# SCH_usb-hub_2024-06-29.net
KiCad netlist of a schematic drawn in EasyEDA
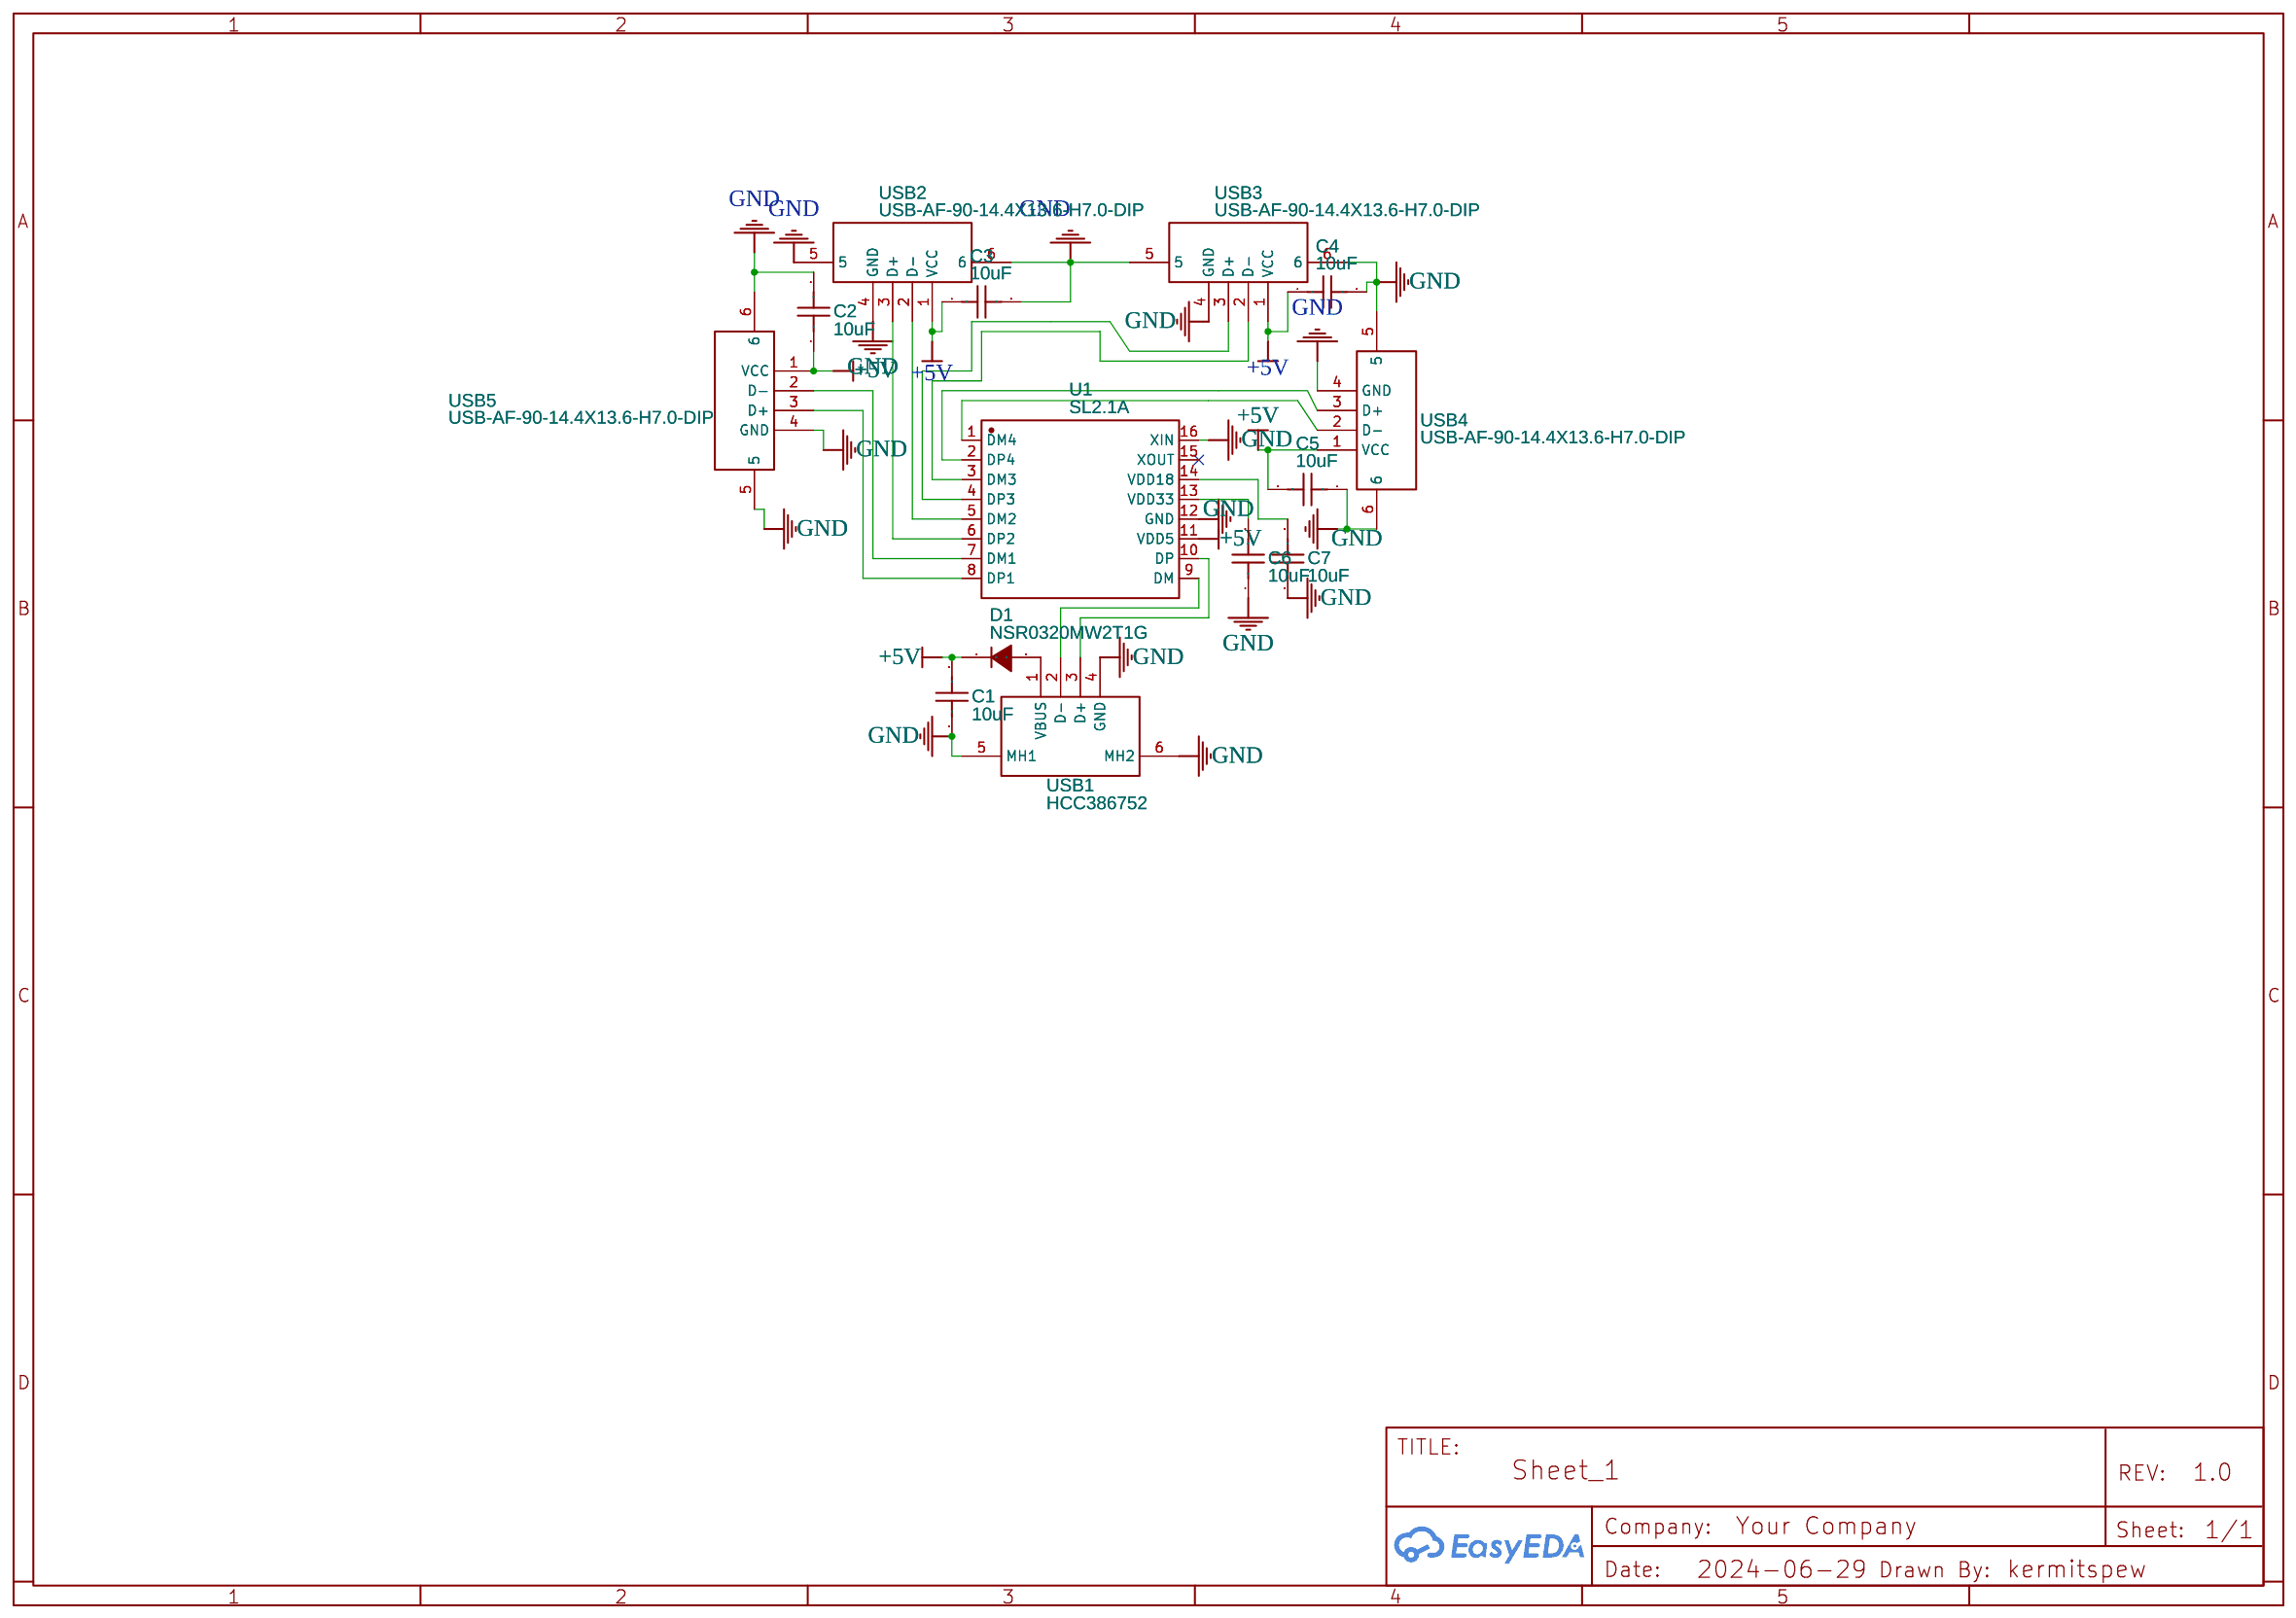
[diagram p0: schematic sheet]

(export (version "E")
  (design (tool "Eeschema 10.0.6"))
  (components
    (comp (ref "C1")
      (value "10uF")
      (fields
        (field (name "Manufacturer Part") "CL10A106KP8NNNC")
        (field (name "Manufacturer") "SAMSUNG(三星)")
      )
      (libsource (lib "") (part "CL10A106KP8NNNC_1"))
    )
    (comp (ref "C2")
      (value "10uF")
      (fields
        (field (name "Manufacturer Part") "CL10A106KP8NNNC")
        (field (name "Manufacturer") "SAMSUNG(三星)")
      )
      (libsource (lib "") (part "CL10A106KP8NNNC_1"))
    )
    (comp (ref "C3")
      (value "10uF")
      (fields
        (field (name "Manufacturer Part") "CL10A106KP8NNNC")
        (field (name "Manufacturer") "SAMSUNG(三星)")
      )
      (libsource (lib "") (part "CL10A106KP8NNNC_2"))
    )
    (comp (ref "C4")
      (value "10uF")
      (fields
        (field (name "Manufacturer Part") "CL10A106KP8NNNC")
        (field (name "Manufacturer") "SAMSUNG(三星)")
      )
      (libsource (lib "") (part "CL10A106KP8NNNC_2"))
    )
    (comp (ref "C5")
      (value "10uF")
      (fields
        (field (name "Manufacturer Part") "CL10A106KP8NNNC")
        (field (name "Manufacturer") "SAMSUNG(三星)")
      )
      (libsource (lib "") (part "CL10A106KP8NNNC"))
    )
    (comp (ref "C6")
      (value "10uF")
      (fields
        (field (name "Manufacturer Part") "CL10A106KP8NNNC")
        (field (name "Manufacturer") "SAMSUNG(三星)")
      )
      (libsource (lib "") (part "CL10A106KP8NNNC_1"))
    )
    (comp (ref "C7")
      (value "10uF")
      (fields
        (field (name "Manufacturer Part") "CL10A106KP8NNNC")
        (field (name "Manufacturer") "SAMSUNG(三星)")
      )
      (libsource (lib "") (part "CL10A106KP8NNNC_1"))
    )
    (comp (ref "D1")
      (value "NSR0320MW2T1G")
      (fields (field (name "Manufacturer") "onsemi(安森美)"))
      (libsource (lib "") (part "NSR0320MW2T1G"))
    )
    (comp (ref "U1")
      (value "SL2.1A")
      (fields (field (name "Manufacturer") "CoreChips(和芯润德)"))
      (libsource (lib "") (part "SL2.1A"))
    )
    (comp (ref "USB1")
      (value "HCC386752")
      (fields (field (name "Manufacturer Part") "U-USBAR04P-M003") (field (name "Manufacturer") "Ckmtw(灿科盟)"))
      (libsource (lib "") (part "HCC386752"))
    )
    (comp (ref "USB2")
      (value "USB-AF-90-14.4X13.6-H7.0-DIP")
      (fields (field (name "Manufacturer Part") "903-131A1011D10100") (field (name "Manufacturer") "精拓金"))
      (libsource (lib "") (part "USB-AF-90-14.4X13.6-H7.0-DIP_2"))
    )
    (comp (ref "USB3")
      (value "USB-AF-90-14.4X13.6-H7.0-DIP")
      (fields (field (name "Manufacturer Part") "903-131A1011D10100") (field (name "Manufacturer") "精拓金"))
      (libsource (lib "") (part "USB-AF-90-14.4X13.6-H7.0-DIP_2"))
    )
    (comp (ref "USB4")
      (value "USB-AF-90-14.4X13.6-H7.0-DIP")
      (fields (field (name "Manufacturer Part") "903-131A1011D10100") (field (name "Manufacturer") "精拓金"))
      (libsource (lib "") (part "USB-AF-90-14.4X13.6-H7.0-DIP_1"))
    )
    (comp (ref "USB5")
      (value "USB-AF-90-14.4X13.6-H7.0-DIP")
      (fields (field (name "Manufacturer Part") "903-131A1011D10100") (field (name "Manufacturer") "精拓金"))
      (libsource (lib "") (part "USB-AF-90-14.4X13.6-H7.0-DIP"))
    )
  )
  (nets
    (net (code "1") (name "+5V") (class "Default")
      (node (ref "C1") (pin "2") (pinfunction "2_2") (pintype "unspecified"))
      (node (ref "C2") (pin "1") (pinfunction "1_1") (pintype "unspecified"))
      (node (ref "C3") (pin "1") (pinfunction "1_1") (pintype "unspecified"))
      (node (ref "C4") (pin "1") (pinfunction "1_1") (pintype "unspecified"))
      (node (ref "C5") (pin "2") (pinfunction "2_2") (pintype "unspecified"))
      (node (ref "D1") (pin "1") (pinfunction "C_1") (pintype "unspecified"))
      (node (ref "U1") (pin "11") (pinfunction "VDD5_11") (pintype "unspecified"))
      (node (ref "USB2") (pin "1") (pinfunction "VCC_1") (pintype "unspecified"))
      (node (ref "USB3") (pin "1") (pinfunction "VCC_1") (pintype "unspecified"))
      (node (ref "USB4") (pin "1") (pinfunction "VCC_1") (pintype "unspecified"))
      (node (ref "USB5") (pin "1") (pinfunction "VCC_1") (pintype "unspecified"))
    )
    (net (code "2") (name "GND") (class "Default")
      (node (ref "C1") (pin "1") (pinfunction "1_1") (pintype "unspecified"))
      (node (ref "C2") (pin "2") (pinfunction "2_2") (pintype "unspecified"))
      (node (ref "C3") (pin "2") (pinfunction "2_2") (pintype "unspecified"))
      (node (ref "C4") (pin "2") (pinfunction "2_2") (pintype "unspecified"))
      (node (ref "C5") (pin "1") (pinfunction "1_1") (pintype "unspecified"))
      (node (ref "C6") (pin "1") (pinfunction "1_1") (pintype "unspecified"))
      (node (ref "C7") (pin "1") (pinfunction "1_1") (pintype "unspecified"))
      (node (ref "U1") (pin "12") (pinfunction "GND_12") (pintype "unspecified"))
      (node (ref "U1") (pin "16") (pinfunction "XIN_16") (pintype "unspecified"))
      (node (ref "USB1") (pin "4") (pinfunction "GND_4") (pintype "unspecified"))
      (node (ref "USB1") (pin "5") (pinfunction "MH1_5") (pintype "unspecified"))
      (node (ref "USB1") (pin "6") (pinfunction "MH2_6") (pintype "unspecified"))
      (node (ref "USB2") (pin "4") (pinfunction "GND_4") (pintype "unspecified"))
      (node (ref "USB2") (pin "5") (pinfunction "5_5") (pintype "unspecified"))
      (node (ref "USB2") (pin "6") (pinfunction "6_6") (pintype "unspecified"))
      (node (ref "USB3") (pin "4") (pinfunction "GND_4") (pintype "unspecified"))
      (node (ref "USB3") (pin "5") (pinfunction "5_5") (pintype "unspecified"))
      (node (ref "USB3") (pin "6") (pinfunction "6_6") (pintype "unspecified"))
      (node (ref "USB4") (pin "4") (pinfunction "GND_4") (pintype "unspecified"))
      (node (ref "USB4") (pin "5") (pinfunction "5_5") (pintype "unspecified"))
      (node (ref "USB4") (pin "6") (pinfunction "6_6") (pintype "unspecified"))
      (node (ref "USB5") (pin "4") (pinfunction "GND_4") (pintype "unspecified"))
      (node (ref "USB5") (pin "5") (pinfunction "5_5") (pintype "unspecified"))
      (node (ref "USB5") (pin "6") (pinfunction "6_6") (pintype "unspecified"))
    )
    (net (code "3") (name "Net-(D1-A)") (class "Default")
      (node (ref "D1") (pin "2") (pinfunction "A_2") (pintype "unspecified"))
      (node (ref "USB1") (pin "1") (pinfunction "VBUS_1") (pintype "unspecified"))
    )
    (net (code "4") (name "Net-(U1-DM)") (class "Default")
      (node (ref "U1") (pin "9") (pinfunction "DM_9") (pintype "unspecified"))
      (node (ref "USB1") (pin "2") (pinfunction "D-_2") (pintype "unspecified"))
    )
    (net (code "5") (name "Net-(U1-DM1)") (class "Default")
      (node (ref "U1") (pin "7") (pinfunction "DM1_7") (pintype "unspecified"))
      (node (ref "USB5") (pin "2") (pinfunction "D-_2") (pintype "unspecified"))
    )
    (net (code "6") (name "Net-(U1-DM2)") (class "Default")
      (node (ref "U1") (pin "5") (pinfunction "DM2_5") (pintype "unspecified"))
      (node (ref "USB2") (pin "2") (pinfunction "D-_2") (pintype "unspecified"))
    )
    (net (code "7") (name "Net-(U1-DM3)") (class "Default")
      (node (ref "U1") (pin "3") (pinfunction "DM3_3") (pintype "unspecified"))
      (node (ref "USB3") (pin "2") (pinfunction "D-_2") (pintype "unspecified"))
    )
    (net (code "8") (name "Net-(U1-DM4)") (class "Default")
      (node (ref "U1") (pin "1") (pinfunction "DM4_1") (pintype "unspecified"))
      (node (ref "USB4") (pin "2") (pinfunction "D-_2") (pintype "unspecified"))
    )
    (net (code "9") (name "Net-(U1-DP)") (class "Default")
      (node (ref "U1") (pin "10") (pinfunction "DP_10") (pintype "unspecified"))
      (node (ref "USB1") (pin "3") (pinfunction "D+_3") (pintype "unspecified"))
    )
    (net (code "10") (name "Net-(U1-DP1)") (class "Default")
      (node (ref "U1") (pin "8") (pinfunction "DP1_8") (pintype "unspecified"))
      (node (ref "USB5") (pin "3") (pinfunction "D+_3") (pintype "unspecified"))
    )
    (net (code "11") (name "Net-(U1-DP2)") (class "Default")
      (node (ref "U1") (pin "6") (pinfunction "DP2_6") (pintype "unspecified"))
      (node (ref "USB2") (pin "3") (pinfunction "D+_3") (pintype "unspecified"))
    )
    (net (code "12") (name "Net-(U1-DP3)") (class "Default")
      (node (ref "U1") (pin "4") (pinfunction "DP3_4") (pintype "unspecified"))
      (node (ref "USB3") (pin "3") (pinfunction "D+_3") (pintype "unspecified"))
    )
    (net (code "13") (name "Net-(U1-DP4)") (class "Default")
      (node (ref "U1") (pin "2") (pinfunction "DP4_2") (pintype "unspecified"))
      (node (ref "USB4") (pin "3") (pinfunction "D+_3") (pintype "unspecified"))
    )
    (net (code "14") (name "Net-(U1-VDD18)") (class "Default")
      (node (ref "C7") (pin "2") (pinfunction "2_2") (pintype "unspecified"))
      (node (ref "U1") (pin "14") (pinfunction "VDD18_14") (pintype "unspecified"))
    )
    (net (code "15") (name "Net-(U1-VDD33)") (class "Default")
      (node (ref "C6") (pin "2") (pinfunction "2_2") (pintype "unspecified"))
      (node (ref "U1") (pin "13") (pinfunction "VDD33_13") (pintype "unspecified"))
    )
    (net (code "16") (name "unconnected-(U1-XOUT-Pad15)") (class "Default")
      (node (ref "U1") (pin "15") (pinfunction "XOUT_15") (pintype "unspecified+no_connect"))
    )
  )
)
